# FPGA_SDRAM1.net
KiCad netlist of a schematic drawn in Altium Designer
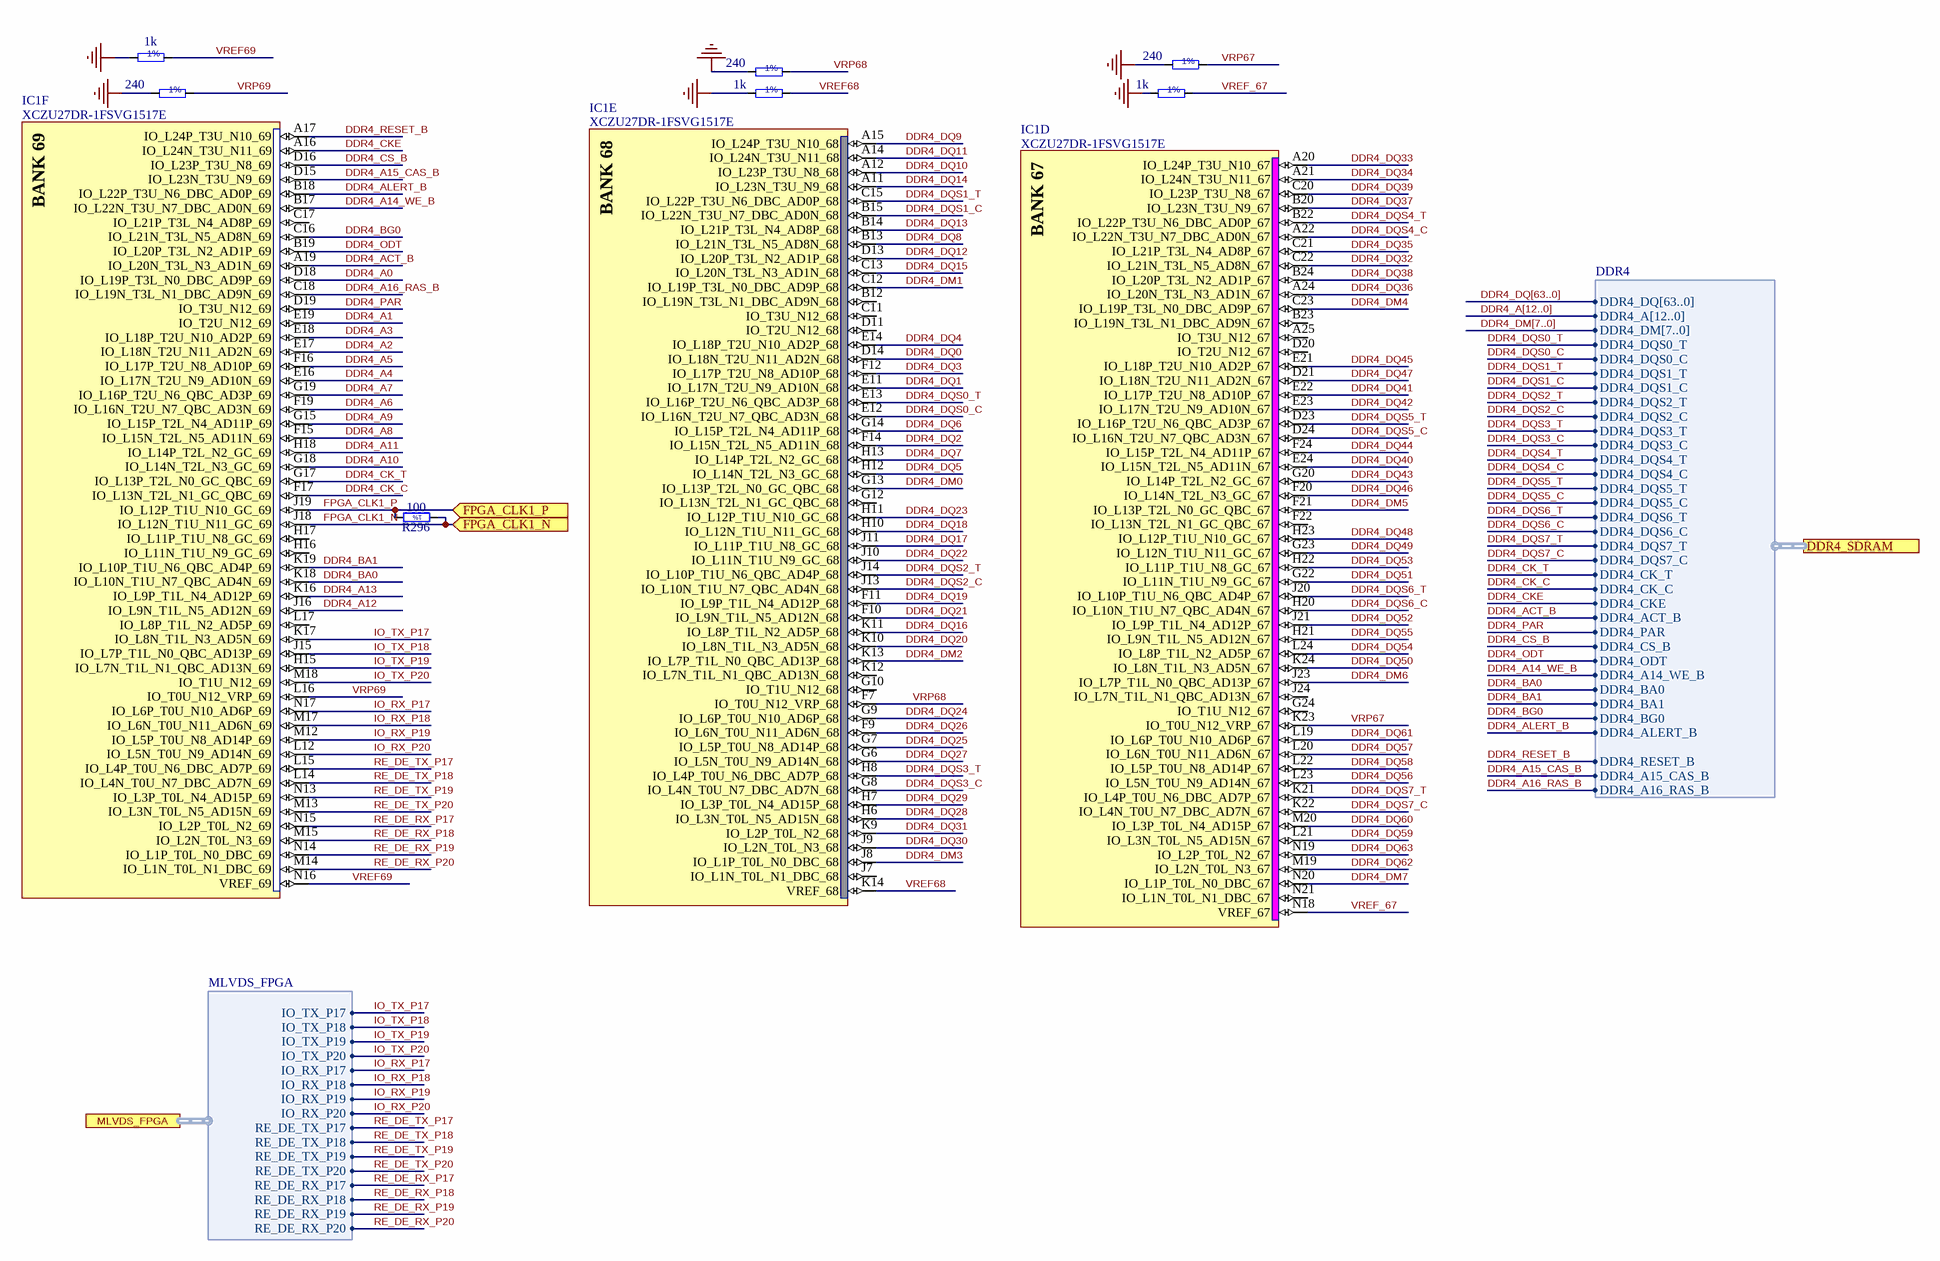
[diagram p0: FPGA_SDRAM1.SchDoc]

(export (version "E")
  (design (tool "Eeschema 10.0.6"))
  (components
    (comp (ref "IC1")
      (value "XCZU27DR-1FSVG1517E")
      (footprint "XILINX_FSVG1517 (XCZU27DR)")
      (fields (field (name "MANUFACTURER") "XILINX") (field (name "AUTHOR") "CERN DEM MR"))
      (libsource (lib "ICs And Semiconductors") (part "XCZU27DR-1FSVG1517E"))
    )
    (comp (ref "R293")
      (value "240")
      (fields
        (field (name "$$NOTCOMMONPROPERTY_GENERAL PART NUMBER") "R0402_240R_1%_0.0625W_100PPM")
        (field (name "$$NOTCOMMONPROPERTY_MANUFACTURER1 PART NUMBER") "232270672401L")
        (field (name "MANUFACTURER") "GENERIC")
      )
      (libsource (lib "altium-import") (part "root_0__*"))
    )
    (comp (ref "R294")
      (value "240")
      (fields
        (field (name "$$NOTCOMMONPROPERTY_GENERAL PART NUMBER") "R0402_240R_1%_0.0625W_100PPM")
        (field (name "$$NOTCOMMONPROPERTY_MANUFACTURER1 PART NUMBER") "232270672401L")
        (field (name "MANUFACTURER") "GENERIC")
      )
      (libsource (lib "altium-import") (part "root_0__*"))
    )
    (comp (ref "R295")
      (value "240")
      (fields
        (field (name "$$NOTCOMMONPROPERTY_GENERAL PART NUMBER") "R0402_240R_1%_0.0625W_100PPM")
        (field (name "$$NOTCOMMONPROPERTY_MANUFACTURER1 PART NUMBER") "232270672401L")
        (field (name "MANUFACTURER") "GENERIC")
      )
      (libsource (lib "altium-import") (part "root_0__*"))
    )
    (comp (ref "R296")
      (value "100")
      (footprint "RESC1005X40N")
      (description "Resistor - 1%")
      (fields
        (field (name "MANUFACTURER PART NUMBER") "R0402_100R_1%_0.0625W_100PPM")
        (field (name "MANUFACTURER") "GENERIC")
        (field (name "AUTHOR") "CERN DEM JLC")
      )
      (libsource (lib "Resistors") (part "Resistor - 1%"))
    )
    (comp (ref "R400")
      (value "1k")
      (fields
        (field (name "$$NOTCOMMONPROPERTY_GENERAL PART NUMBER") "R0402_1K_1%_0.0625W_100PPM")
        (field (name "$$NOTCOMMONPROPERTY_MANUFACTURER1 PART NUMBER") "232270671002L")
        (field (name "MANUFACTURER") "GENERIC")
      )
      (libsource (lib "altium-import") (part "root_0__*"))
    )
    (comp (ref "R451")
      (value "1k")
      (fields
        (field (name "$$NOTCOMMONPROPERTY_GENERAL PART NUMBER") "R0402_1K_1%_0.0625W_100PPM")
        (field (name "$$NOTCOMMONPROPERTY_MANUFACTURER1 PART NUMBER") "232270671002L")
        (field (name "MANUFACTURER") "GENERIC")
      )
      (libsource (lib "altium-import") (part "root_0__*"))
    )
    (comp (ref "R452")
      (value "1k")
      (fields
        (field (name "$$NOTCOMMONPROPERTY_GENERAL PART NUMBER") "R0402_1K_1%_0.0625W_100PPM")
        (field (name "$$NOTCOMMONPROPERTY_MANUFACTURER1 PART NUMBER") "232270671002L")
        (field (name "MANUFACTURER") "GENERIC")
      )
      (libsource (lib "altium-import") (part "root_0__*"))
    )
  )
  (nets
    (net (code "3") (name "/DDR4_A0") (class "Default")
      (node (ref "IC1") (pin "D18") (pinfunction "IO_L19P_T3L_N0_DBC_AD9P_69_D18") (pintype "bidirectional"))
    )
    (net (code "4") (name "/DDR4_A1") (class "Default")
      (node (ref "IC1") (pin "E19") (pinfunction "IO_T2U_N12_69_E19") (pintype "bidirectional"))
    )
    (net (code "5") (name "/DDR4_A2") (class "Default")
      (node (ref "IC1") (pin "E17") (pinfunction "IO_L18N_T2U_N11_AD2N_69_E17") (pintype "bidirectional"))
    )
    (net (code "6") (name "/DDR4_A3") (class "Default")
      (node (ref "IC1") (pin "E18") (pinfunction "IO_L18P_T2U_N10_AD2P_69_E18") (pintype "bidirectional"))
    )
    (net (code "7") (name "/DDR4_A4") (class "Default")
      (node (ref "IC1") (pin "E16") (pinfunction "IO_L17N_T2U_N9_AD10N_69_E16") (pintype "bidirectional"))
    )
    (net (code "8") (name "/DDR4_A5") (class "Default")
      (node (ref "IC1") (pin "F16") (pinfunction "IO_L17P_T2U_N8_AD10P_69_F16") (pintype "bidirectional"))
    )
    (net (code "9") (name "/DDR4_A6") (class "Default")
      (node (ref "IC1") (pin "F19") (pinfunction "IO_L16N_T2U_N7_QBC_AD3N_69_F19") (pintype "bidirectional"))
    )
    (net (code "10") (name "/DDR4_A7") (class "Default")
      (node (ref "IC1") (pin "G19") (pinfunction "IO_L16P_T2U_N6_QBC_AD3P_69_G19") (pintype "bidirectional"))
    )
    (net (code "11") (name "/DDR4_A8") (class "Default")
      (node (ref "IC1") (pin "F15") (pinfunction "IO_L15N_T2L_N5_AD11N_69_F15") (pintype "bidirectional"))
    )
    (net (code "12") (name "/DDR4_A9") (class "Default")
      (node (ref "IC1") (pin "G15") (pinfunction "IO_L15P_T2L_N4_AD11P_69_G15") (pintype "bidirectional"))
    )
    (net (code "13") (name "/DDR4_A10") (class "Default")
      (node (ref "IC1") (pin "G18") (pinfunction "IO_L14N_T2L_N3_GC_69_G18") (pintype "bidirectional"))
    )
    (net (code "14") (name "/DDR4_A11") (class "Default")
      (node (ref "IC1") (pin "H18") (pinfunction "IO_L14P_T2L_N2_GC_69_H18") (pintype "bidirectional"))
    )
    (net (code "15") (name "/DDR4_A12") (class "Default")
      (node (ref "IC1") (pin "J16") (pinfunction "IO_L9N_T1L_N5_AD12N_69_J16") (pintype "bidirectional"))
    )
    (net (code "16") (name "/DDR4_A13") (class "Default")
      (node (ref "IC1") (pin "K16") (pinfunction "IO_L9P_T1L_N4_AD12P_69_K16") (pintype "bidirectional"))
    )
    (net (code "17") (name "/DDR4_A14_WE_B") (class "Default")
      (node (ref "IC1") (pin "B17") (pinfunction "IO_L22N_T3U_N7_DBC_AD0N_69_B17") (pintype "bidirectional"))
    )
    (net (code "18") (name "/DDR4_A15_CAS_B") (class "Default")
      (node (ref "IC1") (pin "D15") (pinfunction "IO_L23N_T3U_N9_69_D15") (pintype "bidirectional"))
    )
    (net (code "19") (name "/DDR4_A16_RAS_B") (class "Default")
      (node (ref "IC1") (pin "C18") (pinfunction "IO_L19N_T3L_N1_DBC_AD9N_69_C18") (pintype "bidirectional"))
    )
    (net (code "20") (name "/DDR4_ACT_B") (class "Default")
      (node (ref "IC1") (pin "A19") (pinfunction "IO_L20N_T3L_N3_AD1N_69_A19") (pintype "bidirectional"))
    )
    (net (code "21") (name "/DDR4_ALERT_B") (class "Default")
      (node (ref "IC1") (pin "B18") (pinfunction "IO_L22P_T3U_N6_DBC_AD0P_69_B18") (pintype "bidirectional"))
    )
    (net (code "23") (name "/DDR4_BA0") (class "Default")
      (node (ref "IC1") (pin "K18") (pinfunction "IO_L10N_T1U_N7_QBC_AD4N_69_K18") (pintype "bidirectional"))
    )
    (net (code "24") (name "/DDR4_BA1") (class "Default")
      (node (ref "IC1") (pin "K19") (pinfunction "IO_L10P_T1U_N6_QBC_AD4P_69_K19") (pintype "bidirectional"))
    )
    (net (code "25") (name "/DDR4_BG0") (class "Default")
      (node (ref "IC1") (pin "C16") (pinfunction "IO_L21N_T3L_N5_AD8N_69_C16") (pintype "bidirectional"))
    )
    (net (code "26") (name "/DDR4_CKE") (class "Default")
      (node (ref "IC1") (pin "A16") (pinfunction "IO_L24N_T3U_N11_69_A16") (pintype "bidirectional"))
    )
    (net (code "27") (name "/DDR4_CK_C") (class "Default")
      (node (ref "IC1") (pin "F17") (pinfunction "IO_L13N_T2L_N1_GC_QBC_69_F17") (pintype "bidirectional"))
    )
    (net (code "28") (name "/DDR4_CK_T") (class "Default")
      (node (ref "IC1") (pin "G17") (pinfunction "IO_L13P_T2L_N0_GC_QBC_69_G17") (pintype "bidirectional"))
    )
    (net (code "29") (name "/DDR4_CS_B") (class "Default")
      (node (ref "IC1") (pin "D16") (pinfunction "IO_L23P_T3U_N8_69_D16") (pintype "bidirectional"))
    )
    (net (code "30") (name "/DDR4_DM0") (class "Default")
      (node (ref "IC1") (pin "G13") (pinfunction "IO_L13P_T2L_N0_GC_QBC_68_G13") (pintype "bidirectional"))
    )
    (net (code "31") (name "/DDR4_DM1") (class "Default")
      (node (ref "IC1") (pin "C12") (pinfunction "IO_L19P_T3L_N0_DBC_AD9P_68_C12") (pintype "bidirectional"))
    )
    (net (code "32") (name "/DDR4_DM2") (class "Default")
      (node (ref "IC1") (pin "K13") (pinfunction "IO_L7P_T1L_N0_QBC_AD13P_68_K13") (pintype "bidirectional"))
    )
    (net (code "33") (name "/DDR4_DM3") (class "Default")
      (node (ref "IC1") (pin "J8") (pinfunction "IO_L1P_T0L_N0_DBC_68_J8") (pintype "bidirectional"))
    )
    (net (code "34") (name "/DDR4_DM4") (class "Default")
      (node (ref "IC1") (pin "C23") (pinfunction "IO_L19P_T3L_N0_DBC_AD9P_67_C23") (pintype "bidirectional"))
    )
    (net (code "35") (name "/DDR4_DM5") (class "Default")
      (node (ref "IC1") (pin "F21") (pinfunction "IO_L13P_T2L_N0_GC_QBC_67_F21") (pintype "bidirectional"))
    )
    (net (code "36") (name "/DDR4_DM6") (class "Default")
      (node (ref "IC1") (pin "J23") (pinfunction "IO_L7P_T1L_N0_QBC_AD13P_67_J23") (pintype "bidirectional"))
    )
    (net (code "37") (name "/DDR4_DM7") (class "Default")
      (node (ref "IC1") (pin "N20") (pinfunction "IO_L1P_T0L_N0_DBC_67_N20") (pintype "bidirectional"))
    )
    (net (code "39") (name "/DDR4_DQ0") (class "Default")
      (node (ref "IC1") (pin "D14") (pinfunction "IO_L18N_T2U_N11_AD2N_68_D14") (pintype "bidirectional"))
    )
    (net (code "40") (name "/DDR4_DQ1") (class "Default")
      (node (ref "IC1") (pin "E11") (pinfunction "IO_L17N_T2U_N9_AD10N_68_E11") (pintype "bidirectional"))
    )
    (net (code "41") (name "/DDR4_DQ2") (class "Default")
      (node (ref "IC1") (pin "F14") (pinfunction "IO_L15N_T2L_N5_AD11N_68_F14") (pintype "bidirectional"))
    )
    (net (code "42") (name "/DDR4_DQ3") (class "Default")
      (node (ref "IC1") (pin "F12") (pinfunction "IO_L17P_T2U_N8_AD10P_68_F12") (pintype "bidirectional"))
    )
    (net (code "43") (name "/DDR4_DQ4") (class "Default")
      (node (ref "IC1") (pin "E14") (pinfunction "IO_L18P_T2U_N10_AD2P_68_E14") (pintype "bidirectional"))
    )
    (net (code "44") (name "/DDR4_DQ5") (class "Default")
      (node (ref "IC1") (pin "H12") (pinfunction "IO_L14N_T2L_N3_GC_68_H12") (pintype "bidirectional"))
    )
    (net (code "45") (name "/DDR4_DQ6") (class "Default")
      (node (ref "IC1") (pin "G14") (pinfunction "IO_L15P_T2L_N4_AD11P_68_G14") (pintype "bidirectional"))
    )
    (net (code "46") (name "/DDR4_DQ7") (class "Default")
      (node (ref "IC1") (pin "H13") (pinfunction "IO_L14P_T2L_N2_GC_68_H13") (pintype "bidirectional"))
    )
    (net (code "47") (name "/DDR4_DQ8") (class "Default")
      (node (ref "IC1") (pin "B13") (pinfunction "IO_L21N_T3L_N5_AD8N_68_B13") (pintype "bidirectional"))
    )
    (net (code "48") (name "/DDR4_DQ9") (class "Default")
      (node (ref "IC1") (pin "A15") (pinfunction "IO_L24P_T3U_N10_68_A15") (pintype "bidirectional"))
    )
    (net (code "49") (name "/DDR4_DQ10") (class "Default")
      (node (ref "IC1") (pin "A12") (pinfunction "IO_L23P_T3U_N8_68_A12") (pintype "bidirectional"))
    )
    (net (code "50") (name "/DDR4_DQ11") (class "Default")
      (node (ref "IC1") (pin "A14") (pinfunction "IO_L24N_T3U_N11_68_A14") (pintype "bidirectional"))
    )
    (net (code "51") (name "/DDR4_DQ12") (class "Default")
      (node (ref "IC1") (pin "D13") (pinfunction "IO_L20P_T3L_N2_AD1P_68_D13") (pintype "bidirectional"))
    )
    (net (code "52") (name "/DDR4_DQ13") (class "Default")
      (node (ref "IC1") (pin "B14") (pinfunction "IO_L21P_T3L_N4_AD8P_68_B14") (pintype "bidirectional"))
    )
    (net (code "53") (name "/DDR4_DQ14") (class "Default")
      (node (ref "IC1") (pin "A11") (pinfunction "IO_L23N_T3U_N9_68_A11") (pintype "bidirectional"))
    )
    (net (code "54") (name "/DDR4_DQ15") (class "Default")
      (node (ref "IC1") (pin "C13") (pinfunction "IO_L20N_T3L_N3_AD1N_68_C13") (pintype "bidirectional"))
    )
    (net (code "55") (name "/DDR4_DQ16") (class "Default")
      (node (ref "IC1") (pin "K11") (pinfunction "IO_L8P_T1L_N2_AD5P_68_K11") (pintype "bidirectional"))
    )
    (net (code "56") (name "/DDR4_DQ17") (class "Default")
      (node (ref "IC1") (pin "J11") (pinfunction "IO_L11P_T1U_N8_GC_68_J11") (pintype "bidirectional"))
    )
    (net (code "57") (name "/DDR4_DQ18") (class "Default")
      (node (ref "IC1") (pin "H10") (pinfunction "IO_L12N_T1U_N11_GC_68_H10") (pintype "bidirectional"))
    )
    (net (code "58") (name "/DDR4_DQ19") (class "Default")
      (node (ref "IC1") (pin "F11") (pinfunction "IO_L9P_T1L_N4_AD12P_68_F11") (pintype "bidirectional"))
    )
    (net (code "59") (name "/DDR4_DQ20") (class "Default")
      (node (ref "IC1") (pin "K10") (pinfunction "IO_L8N_T1L_N3_AD5N_68_K10") (pintype "bidirectional"))
    )
    (net (code "60") (name "/DDR4_DQ21") (class "Default")
      (node (ref "IC1") (pin "F10") (pinfunction "IO_L9N_T1L_N5_AD12N_68_F10") (pintype "bidirectional"))
    )
    (net (code "61") (name "/DDR4_DQ22") (class "Default")
      (node (ref "IC1") (pin "J10") (pinfunction "IO_L11N_T1U_N9_GC_68_J10") (pintype "bidirectional"))
    )
    (net (code "62") (name "/DDR4_DQ23") (class "Default")
      (node (ref "IC1") (pin "H11") (pinfunction "IO_L12P_T1U_N10_GC_68_H11") (pintype "bidirectional"))
    )
    (net (code "63") (name "/DDR4_DQ24") (class "Default")
      (node (ref "IC1") (pin "G9") (pinfunction "IO_L6P_T0U_N10_AD6P_68_G9") (pintype "bidirectional"))
    )
    (net (code "64") (name "/DDR4_DQ25") (class "Default")
      (node (ref "IC1") (pin "G7") (pinfunction "IO_L5P_T0U_N8_AD14P_68_G7") (pintype "bidirectional"))
    )
    (net (code "65") (name "/DDR4_DQ26") (class "Default")
      (node (ref "IC1") (pin "F9") (pinfunction "IO_L6N_T0U_N11_AD6N_68_F9") (pintype "bidirectional"))
    )
    (net (code "66") (name "/DDR4_DQ27") (class "Default")
      (node (ref "IC1") (pin "G6") (pinfunction "IO_L5N_T0U_N9_AD14N_68_G6") (pintype "bidirectional"))
    )
    (net (code "67") (name "/DDR4_DQ28") (class "Default")
      (node (ref "IC1") (pin "H6") (pinfunction "IO_L3N_T0L_N5_AD15N_68_H6") (pintype "bidirectional"))
    )
    (net (code "68") (name "/DDR4_DQ29") (class "Default")
      (node (ref "IC1") (pin "H7") (pinfunction "IO_L3P_T0L_N4_AD15P_68_H7") (pintype "bidirectional"))
    )
    (net (code "69") (name "/DDR4_DQ30") (class "Default")
      (node (ref "IC1") (pin "J9") (pinfunction "IO_L2N_T0L_N3_68_J9") (pintype "bidirectional"))
    )
    (net (code "70") (name "/DDR4_DQ31") (class "Default")
      (node (ref "IC1") (pin "K9") (pinfunction "IO_L2P_T0L_N2_68_K9") (pintype "bidirectional"))
    )
    (net (code "71") (name "/DDR4_DQ32") (class "Default")
      (node (ref "IC1") (pin "C22") (pinfunction "IO_L21N_T3L_N5_AD8N_67_C22") (pintype "bidirectional"))
    )
    (net (code "72") (name "/DDR4_DQ33") (class "Default")
      (node (ref "IC1") (pin "A20") (pinfunction "IO_L24P_T3U_N10_67_A20") (pintype "bidirectional"))
    )
    (net (code "73") (name "/DDR4_DQ34") (class "Default")
      (node (ref "IC1") (pin "A21") (pinfunction "IO_L24N_T3U_N11_67_A21") (pintype "bidirectional"))
    )
    (net (code "74") (name "/DDR4_DQ35") (class "Default")
      (node (ref "IC1") (pin "C21") (pinfunction "IO_L21P_T3L_N4_AD8P_67_C21") (pintype "bidirectional"))
    )
    (net (code "75") (name "/DDR4_DQ36") (class "Default")
      (node (ref "IC1") (pin "A24") (pinfunction "IO_L20N_T3L_N3_AD1N_67_A24") (pintype "bidirectional"))
    )
    (net (code "76") (name "/DDR4_DQ37") (class "Default")
      (node (ref "IC1") (pin "B20") (pinfunction "IO_L23N_T3U_N9_67_B20") (pintype "bidirectional"))
    )
    (net (code "77") (name "/DDR4_DQ38") (class "Default")
      (node (ref "IC1") (pin "B24") (pinfunction "IO_L20P_T3L_N2_AD1P_67_B24") (pintype "bidirectional"))
    )
    (net (code "78") (name "/DDR4_DQ39") (class "Default")
      (node (ref "IC1") (pin "C20") (pinfunction "IO_L23P_T3U_N8_67_C20") (pintype "bidirectional"))
    )
    (net (code "79") (name "/DDR4_DQ40") (class "Default")
      (node (ref "IC1") (pin "E24") (pinfunction "IO_L15N_T2L_N5_AD11N_67_E24") (pintype "bidirectional"))
    )
    (net (code "80") (name "/DDR4_DQ41") (class "Default")
      (node (ref "IC1") (pin "E22") (pinfunction "IO_L17P_T2U_N8_AD10P_67_E22") (pintype "bidirectional"))
    )
    (net (code "81") (name "/DDR4_DQ42") (class "Default")
      (node (ref "IC1") (pin "E23") (pinfunction "IO_L17N_T2U_N9_AD10N_67_E23") (pintype "bidirectional"))
    )
    (net (code "82") (name "/DDR4_DQ43") (class "Default")
      (node (ref "IC1") (pin "G20") (pinfunction "IO_L14P_T2L_N2_GC_67_G20") (pintype "bidirectional"))
    )
    (net (code "83") (name "/DDR4_DQ44") (class "Default")
      (node (ref "IC1") (pin "F24") (pinfunction "IO_L15P_T2L_N4_AD11P_67_F24") (pintype "bidirectional"))
    )
    (net (code "84") (name "/DDR4_DQ45") (class "Default")
      (node (ref "IC1") (pin "E21") (pinfunction "IO_L18P_T2U_N10_AD2P_67_E21") (pintype "bidirectional"))
    )
    (net (code "85") (name "/DDR4_DQ46") (class "Default")
      (node (ref "IC1") (pin "F20") (pinfunction "IO_L14N_T2L_N3_GC_67_F20") (pintype "bidirectional"))
    )
    (net (code "86") (name "/DDR4_DQ47") (class "Default")
      (node (ref "IC1") (pin "D21") (pinfunction "IO_L18N_T2U_N11_AD2N_67_D21") (pintype "bidirectional"))
    )
    (net (code "87") (name "/DDR4_DQ48") (class "Default")
      (node (ref "IC1") (pin "H23") (pinfunction "IO_L12P_T1U_N10_GC_67_H23") (pintype "bidirectional"))
    )
    (net (code "88") (name "/DDR4_DQ49") (class "Default")
      (node (ref "IC1") (pin "G23") (pinfunction "IO_L12N_T1U_N11_GC_67_G23") (pintype "bidirectional"))
    )
    (net (code "89") (name "/DDR4_DQ50") (class "Default")
      (node (ref "IC1") (pin "K24") (pinfunction "IO_L8N_T1L_N3_AD5N_67_K24") (pintype "bidirectional"))
    )
    (net (code "90") (name "/DDR4_DQ51") (class "Default")
      (node (ref "IC1") (pin "G22") (pinfunction "IO_L11N_T1U_N9_GC_67_G22") (pintype "bidirectional"))
    )
    (net (code "91") (name "/DDR4_DQ52") (class "Default")
      (node (ref "IC1") (pin "J21") (pinfunction "IO_L9P_T1L_N4_AD12P_67_J21") (pintype "bidirectional"))
    )
    (net (code "92") (name "/DDR4_DQ53") (class "Default")
      (node (ref "IC1") (pin "H22") (pinfunction "IO_L11P_T1U_N8_GC_67_H22") (pintype "bidirectional"))
    )
    (net (code "93") (name "/DDR4_DQ54") (class "Default")
      (node (ref "IC1") (pin "L24") (pinfunction "IO_L8P_T1L_N2_AD5P_67_L24") (pintype "bidirectional"))
    )
    (net (code "94") (name "/DDR4_DQ55") (class "Default")
      (node (ref "IC1") (pin "H21") (pinfunction "IO_L9N_T1L_N5_AD12N_67_H21") (pintype "bidirectional"))
    )
    (net (code "95") (name "/DDR4_DQ56") (class "Default")
      (node (ref "IC1") (pin "L23") (pinfunction "IO_L5N_T0U_N9_AD14N_67_L23") (pintype "bidirectional"))
    )
    (net (code "96") (name "/DDR4_DQ57") (class "Default")
      (node (ref "IC1") (pin "L20") (pinfunction "IO_L6N_T0U_N11_AD6N_67_L20") (pintype "bidirectional"))
    )
    (net (code "97") (name "/DDR4_DQ58") (class "Default")
      (node (ref "IC1") (pin "L22") (pinfunction "IO_L5P_T0U_N8_AD14P_67_L22") (pintype "bidirectional"))
    )
    (net (code "98") (name "/DDR4_DQ59") (class "Default")
      (node (ref "IC1") (pin "L21") (pinfunction "IO_L3N_T0L_N5_AD15N_67_L21") (pintype "bidirectional"))
    )
    (net (code "99") (name "/DDR4_DQ60") (class "Default")
      (node (ref "IC1") (pin "M20") (pinfunction "IO_L3P_T0L_N4_AD15P_67_M20") (pintype "bidirectional"))
    )
    (net (code "100") (name "/DDR4_DQ61") (class "Default")
      (node (ref "IC1") (pin "L19") (pinfunction "IO_L6P_T0U_N10_AD6P_67_L19") (pintype "bidirectional"))
    )
    (net (code "101") (name "/DDR4_DQ62") (class "Default")
      (node (ref "IC1") (pin "M19") (pinfunction "IO_L2N_T0L_N3_67_M19") (pintype "bidirectional"))
    )
    (net (code "102") (name "/DDR4_DQ63") (class "Default")
      (node (ref "IC1") (pin "N19") (pinfunction "IO_L2P_T0L_N2_67_N19") (pintype "bidirectional"))
    )
    (net (code "103") (name "/DDR4_DQS0_C") (class "Default")
      (node (ref "IC1") (pin "E12") (pinfunction "IO_L16N_T2U_N7_QBC_AD3N_68_E12") (pintype "bidirectional"))
    )
    (net (code "104") (name "/DDR4_DQS0_T") (class "Default")
      (node (ref "IC1") (pin "E13") (pinfunction "IO_L16P_T2U_N6_QBC_AD3P_68_E13") (pintype "bidirectional"))
    )
    (net (code "105") (name "/DDR4_DQS1_C") (class "Default")
      (node (ref "IC1") (pin "B15") (pinfunction "IO_L22N_T3U_N7_DBC_AD0N_68_B15") (pintype "bidirectional"))
    )
    (net (code "106") (name "/DDR4_DQS1_T") (class "Default")
      (node (ref "IC1") (pin "C15") (pinfunction "IO_L22P_T3U_N6_DBC_AD0P_68_C15") (pintype "bidirectional"))
    )
    (net (code "107") (name "/DDR4_DQS2_C") (class "Default")
      (node (ref "IC1") (pin "J13") (pinfunction "IO_L10N_T1U_N7_QBC_AD4N_68_J13") (pintype "bidirectional"))
    )
    (net (code "108") (name "/DDR4_DQS2_T") (class "Default")
      (node (ref "IC1") (pin "J14") (pinfunction "IO_L10P_T1U_N6_QBC_AD4P_68_J14") (pintype "bidirectional"))
    )
    (net (code "109") (name "/DDR4_DQS3_C") (class "Default")
      (node (ref "IC1") (pin "G8") (pinfunction "IO_L4N_T0U_N7_DBC_AD7N_68_G8") (pintype "bidirectional"))
    )
    (net (code "110") (name "/DDR4_DQS3_T") (class "Default")
      (node (ref "IC1") (pin "H8") (pinfunction "IO_L4P_T0U_N6_DBC_AD7P_68_H8") (pintype "bidirectional"))
    )
    (net (code "111") (name "/DDR4_DQS4_C") (class "Default")
      (node (ref "IC1") (pin "A22") (pinfunction "IO_L22N_T3U_N7_DBC_AD0N_67_A22") (pintype "bidirectional"))
    )
    (net (code "112") (name "/DDR4_DQS4_T") (class "Default")
      (node (ref "IC1") (pin "B22") (pinfunction "IO_L22P_T3U_N6_DBC_AD0P_67_B22") (pintype "bidirectional"))
    )
    (net (code "113") (name "/DDR4_DQS5_C") (class "Default")
      (node (ref "IC1") (pin "D24") (pinfunction "IO_L16N_T2U_N7_QBC_AD3N_67_D24") (pintype "bidirectional"))
    )
    (net (code "114") (name "/DDR4_DQS5_T") (class "Default")
      (node (ref "IC1") (pin "D23") (pinfunction "IO_L16P_T2U_N6_QBC_AD3P_67_D23") (pintype "bidirectional"))
    )
    (net (code "115") (name "/DDR4_DQS6_C") (class "Default")
      (node (ref "IC1") (pin "H20") (pinfunction "IO_L10N_T1U_N7_QBC_AD4N_67_H20") (pintype "bidirectional"))
    )
    (net (code "116") (name "/DDR4_DQS6_T") (class "Default")
      (node (ref "IC1") (pin "J20") (pinfunction "IO_L10P_T1U_N6_QBC_AD4P_67_J20") (pintype "bidirectional"))
    )
    (net (code "117") (name "/DDR4_DQS7_C") (class "Default")
      (node (ref "IC1") (pin "K22") (pinfunction "IO_L4N_T0U_N7_DBC_AD7N_67_K22") (pintype "bidirectional"))
    )
    (net (code "118") (name "/DDR4_DQS7_T") (class "Default")
      (node (ref "IC1") (pin "K21") (pinfunction "IO_L4P_T0U_N6_DBC_AD7P_67_K21") (pintype "bidirectional"))
    )
    (net (code "119") (name "/DDR4_ODT") (class "Default")
      (node (ref "IC1") (pin "B19") (pinfunction "IO_L20P_T3L_N2_AD1P_69_B19") (pintype "bidirectional"))
    )
    (net (code "120") (name "/DDR4_PAR") (class "Default")
      (node (ref "IC1") (pin "D19") (pinfunction "IO_T3U_N12_69_D19") (pintype "bidirectional"))
    )
    (net (code "121") (name "/DDR4_RESET_B") (class "Default")
      (node (ref "IC1") (pin "A17") (pinfunction "IO_L24P_T3U_N10_69_A17") (pintype "bidirectional"))
    )
    (net (code "123") (name "/FPGA_CLK1_N") (class "Default")
      (node (ref "IC1") (pin "J18") (pinfunction "IO_L12N_T1U_N11_GC_69_J18") (pintype "bidirectional"))
      (node (ref "R296") (pin "2") (pinfunction "2_2") (pintype "passive"))
    )
    (net (code "124") (name "/FPGA_CLK1_P") (class "Default")
      (node (ref "IC1") (pin "J19") (pinfunction "IO_L12P_T1U_N10_GC_69_J19") (pintype "bidirectional"))
      (node (ref "R296") (pin "1") (pinfunction "1_1") (pintype "passive"))
    )
    (net (code "125") (name "/IO_RX_P17") (class "Default")
      (node (ref "IC1") (pin "N17") (pinfunction "IO_L6P_T0U_N10_AD6P_69_N17") (pintype "bidirectional"))
    )
    (net (code "126") (name "/IO_RX_P18") (class "Default")
      (node (ref "IC1") (pin "M17") (pinfunction "IO_L6N_T0U_N11_AD6N_69_M17") (pintype "bidirectional"))
    )
    (net (code "127") (name "/IO_RX_P19") (class "Default")
      (node (ref "IC1") (pin "M12") (pinfunction "IO_L5P_T0U_N8_AD14P_69_M12") (pintype "bidirectional"))
    )
    (net (code "128") (name "/IO_RX_P20") (class "Default")
      (node (ref "IC1") (pin "L12") (pinfunction "IO_L5N_T0U_N9_AD14N_69_L12") (pintype "bidirectional"))
    )
    (net (code "129") (name "/IO_TX_P17") (class "Default")
      (node (ref "IC1") (pin "K17") (pinfunction "IO_L8N_T1L_N3_AD5N_69_K17") (pintype "bidirectional"))
    )
    (net (code "130") (name "/IO_TX_P18") (class "Default")
      (node (ref "IC1") (pin "J15") (pinfunction "IO_L7P_T1L_N0_QBC_AD13P_69_J15") (pintype "bidirectional"))
    )
    (net (code "131") (name "/IO_TX_P19") (class "Default")
      (node (ref "IC1") (pin "H15") (pinfunction "IO_L7N_T1L_N1_QBC_AD13N_69_H15") (pintype "bidirectional"))
    )
    (net (code "132") (name "/IO_TX_P20") (class "Default")
      (node (ref "IC1") (pin "M18") (pinfunction "IO_T1U_N12_69_M18") (pintype "bidirectional"))
    )
    (net (code "133") (name "/RE_DE_RX_P17") (class "Default")
      (node (ref "IC1") (pin "N15") (pinfunction "IO_L2P_T0L_N2_69_N15") (pintype "bidirectional"))
    )
    (net (code "134") (name "/RE_DE_RX_P18") (class "Default")
      (node (ref "IC1") (pin "M15") (pinfunction "IO_L2N_T0L_N3_69_M15") (pintype "bidirectional"))
    )
    (net (code "135") (name "/RE_DE_RX_P19") (class "Default")
      (node (ref "IC1") (pin "N14") (pinfunction "IO_L1P_T0L_N0_DBC_69_N14") (pintype "bidirectional"))
    )
    (net (code "136") (name "/RE_DE_RX_P20") (class "Default")
      (node (ref "IC1") (pin "M14") (pinfunction "IO_L1N_T0L_N1_DBC_69_M14") (pintype "bidirectional"))
    )
    (net (code "137") (name "/RE_DE_TX_P17") (class "Default")
      (node (ref "IC1") (pin "L15") (pinfunction "IO_L4P_T0U_N6_DBC_AD7P_69_L15") (pintype "bidirectional"))
    )
    (net (code "138") (name "/RE_DE_TX_P18") (class "Default")
      (node (ref "IC1") (pin "L14") (pinfunction "IO_L4N_T0U_N7_DBC_AD7N_69_L14") (pintype "bidirectional"))
    )
    (net (code "139") (name "/RE_DE_TX_P19") (class "Default")
      (node (ref "IC1") (pin "N13") (pinfunction "IO_L3P_T0L_N4_AD15P_69_N13") (pintype "bidirectional"))
    )
    (net (code "140") (name "/RE_DE_TX_P20") (class "Default")
      (node (ref "IC1") (pin "M13") (pinfunction "IO_L3N_T0L_N5_AD15N_69_M13") (pintype "bidirectional"))
    )
    (net (code "141") (name "/VREF68") (class "Default")
      (node (ref "IC1") (pin "K14") (pinfunction "VREF_68_K14") (pintype "bidirectional"))
      (node (ref "R451") (pin "2") (pinfunction "2_2") (pintype "passive"))
    )
    (net (code "142") (name "/VREF69") (class "Default")
      (node (ref "IC1") (pin "N16") (pinfunction "VREF_69_N16") (pintype "bidirectional"))
      (node (ref "R400") (pin "2") (pinfunction "2_2") (pintype "passive"))
    )
    (net (code "143") (name "/VREF_67") (class "Default")
      (node (ref "IC1") (pin "N18") (pinfunction "VREF_67_N18") (pintype "bidirectional"))
      (node (ref "R452") (pin "2") (pinfunction "2_2") (pintype "passive"))
    )
    (net (code "144") (name "/VRP67") (class "Default")
      (node (ref "IC1") (pin "K23") (pinfunction "IO_T0U_N12_VRP_67_K23") (pintype "bidirectional"))
      (node (ref "R295") (pin "2") (pinfunction "2_2") (pintype "passive"))
    )
    (net (code "145") (name "/VRP68") (class "Default")
      (node (ref "IC1") (pin "F7") (pinfunction "IO_T0U_N12_VRP_68_F7") (pintype "bidirectional"))
      (node (ref "R294") (pin "2") (pinfunction "2_2") (pintype "passive"))
    )
    (net (code "146") (name "/VRP69") (class "Default")
      (node (ref "IC1") (pin "L16") (pinfunction "IO_T0U_N12_VRP_69_L16") (pintype "bidirectional"))
      (node (ref "R293") (pin "2") (pinfunction "2_2") (pintype "passive"))
    )
    (net (code "149") (name "GND") (class "Default")
      (node (ref "R293") (pin "1") (pinfunction "1_1") (pintype "passive"))
      (node (ref "R294") (pin "1") (pinfunction "1_1") (pintype "passive"))
      (node (ref "R295") (pin "1") (pinfunction "1_1") (pintype "passive"))
      (node (ref "R400") (pin "1") (pinfunction "1_1") (pintype "passive"))
      (node (ref "R451") (pin "1") (pinfunction "1_1") (pintype "passive"))
      (node (ref "R452") (pin "1") (pinfunction "1_1") (pintype "passive"))
    )
    (net (code "150") (name "unconnected-(IC1D-IO_L1N_T0L_N1_DBC_67-PadN21)") (class "Default")
      (node (ref "IC1") (pin "N21") (pinfunction "IO_L1N_T0L_N1_DBC_67_N21") (pintype "bidirectional"))
    )
    (net (code "151") (name "unconnected-(IC1D-IO_L7N_T1L_N1_QBC_AD13N_67-PadJ24)") (class "Default")
      (node (ref "IC1") (pin "J24") (pinfunction "IO_L7N_T1L_N1_QBC_AD13N_67_J24") (pintype "bidirectional"))
    )
    (net (code "152") (name "unconnected-(IC1D-IO_L13N_T2L_N1_GC_QBC_67-PadF22)") (class "Default")
      (node (ref "IC1") (pin "F22") (pinfunction "IO_L13N_T2L_N1_GC_QBC_67_F22") (pintype "bidirectional"))
    )
    (net (code "153") (name "unconnected-(IC1D-IO_L19N_T3L_N1_DBC_AD9N_67-PadB23)") (class "Default")
      (node (ref "IC1") (pin "B23") (pinfunction "IO_L19N_T3L_N1_DBC_AD9N_67_B23") (pintype "bidirectional"))
    )
    (net (code "154") (name "unconnected-(IC1D-IO_T1U_N12_67-PadG24)") (class "Default")
      (node (ref "IC1") (pin "G24") (pinfunction "IO_T1U_N12_67_G24") (pintype "bidirectional"))
    )
    (net (code "155") (name "unconnected-(IC1D-IO_T2U_N12_67-PadD20)") (class "Default")
      (node (ref "IC1") (pin "D20") (pinfunction "IO_T2U_N12_67_D20") (pintype "bidirectional"))
    )
    (net (code "156") (name "unconnected-(IC1D-IO_T3U_N12_67-PadA25)") (class "Default")
      (node (ref "IC1") (pin "A25") (pinfunction "IO_T3U_N12_67_A25") (pintype "bidirectional"))
    )
    (net (code "157") (name "unconnected-(IC1E-IO_L1N_T0L_N1_DBC_68-PadJ7)") (class "Default")
      (node (ref "IC1") (pin "J7") (pinfunction "IO_L1N_T0L_N1_DBC_68_J7") (pintype "bidirectional"))
    )
    (net (code "158") (name "unconnected-(IC1E-IO_L7N_T1L_N1_QBC_AD13N_68-PadK12)") (class "Default")
      (node (ref "IC1") (pin "K12") (pinfunction "IO_L7N_T1L_N1_QBC_AD13N_68_K12") (pintype "bidirectional"))
    )
    (net (code "159") (name "unconnected-(IC1E-IO_L13N_T2L_N1_GC_QBC_68-PadG12)") (class "Default")
      (node (ref "IC1") (pin "G12") (pinfunction "IO_L13N_T2L_N1_GC_QBC_68_G12") (pintype "bidirectional"))
    )
    (net (code "160") (name "unconnected-(IC1E-IO_L19N_T3L_N1_DBC_AD9N_68-PadB12)") (class "Default")
      (node (ref "IC1") (pin "B12") (pinfunction "IO_L19N_T3L_N1_DBC_AD9N_68_B12") (pintype "bidirectional"))
    )
    (net (code "161") (name "unconnected-(IC1E-IO_T1U_N12_68-PadG10)") (class "Default")
      (node (ref "IC1") (pin "G10") (pinfunction "IO_T1U_N12_68_G10") (pintype "bidirectional"))
    )
    (net (code "162") (name "unconnected-(IC1E-IO_T2U_N12_68-PadD11)") (class "Default")
      (node (ref "IC1") (pin "D11") (pinfunction "IO_T2U_N12_68_D11") (pintype "bidirectional"))
    )
    (net (code "163") (name "unconnected-(IC1E-IO_T3U_N12_68-PadC11)") (class "Default")
      (node (ref "IC1") (pin "C11") (pinfunction "IO_T3U_N12_68_C11") (pintype "bidirectional"))
    )
    (net (code "164") (name "unconnected-(IC1F-IO_L8P_T1L_N2_AD5P_69-PadL17)") (class "Default")
      (node (ref "IC1") (pin "L17") (pinfunction "IO_L8P_T1L_N2_AD5P_69_L17") (pintype "bidirectional"))
    )
    (net (code "165") (name "unconnected-(IC1F-IO_L11N_T1U_N9_GC_69-PadH16)") (class "Default")
      (node (ref "IC1") (pin "H16") (pinfunction "IO_L11N_T1U_N9_GC_69_H16") (pintype "bidirectional"))
    )
    (net (code "166") (name "unconnected-(IC1F-IO_L11P_T1U_N8_GC_69-PadH17)") (class "Default")
      (node (ref "IC1") (pin "H17") (pinfunction "IO_L11P_T1U_N8_GC_69_H17") (pintype "bidirectional"))
    )
    (net (code "167") (name "unconnected-(IC1F-IO_L21P_T3L_N4_AD8P_69-PadC17)") (class "Default")
      (node (ref "IC1") (pin "C17") (pinfunction "IO_L21P_T3L_N4_AD8P_69_C17") (pintype "bidirectional"))
    )
  )
)
